# STMKernel144.net
KiCad netlist of a schematic drawn in Altium Designer
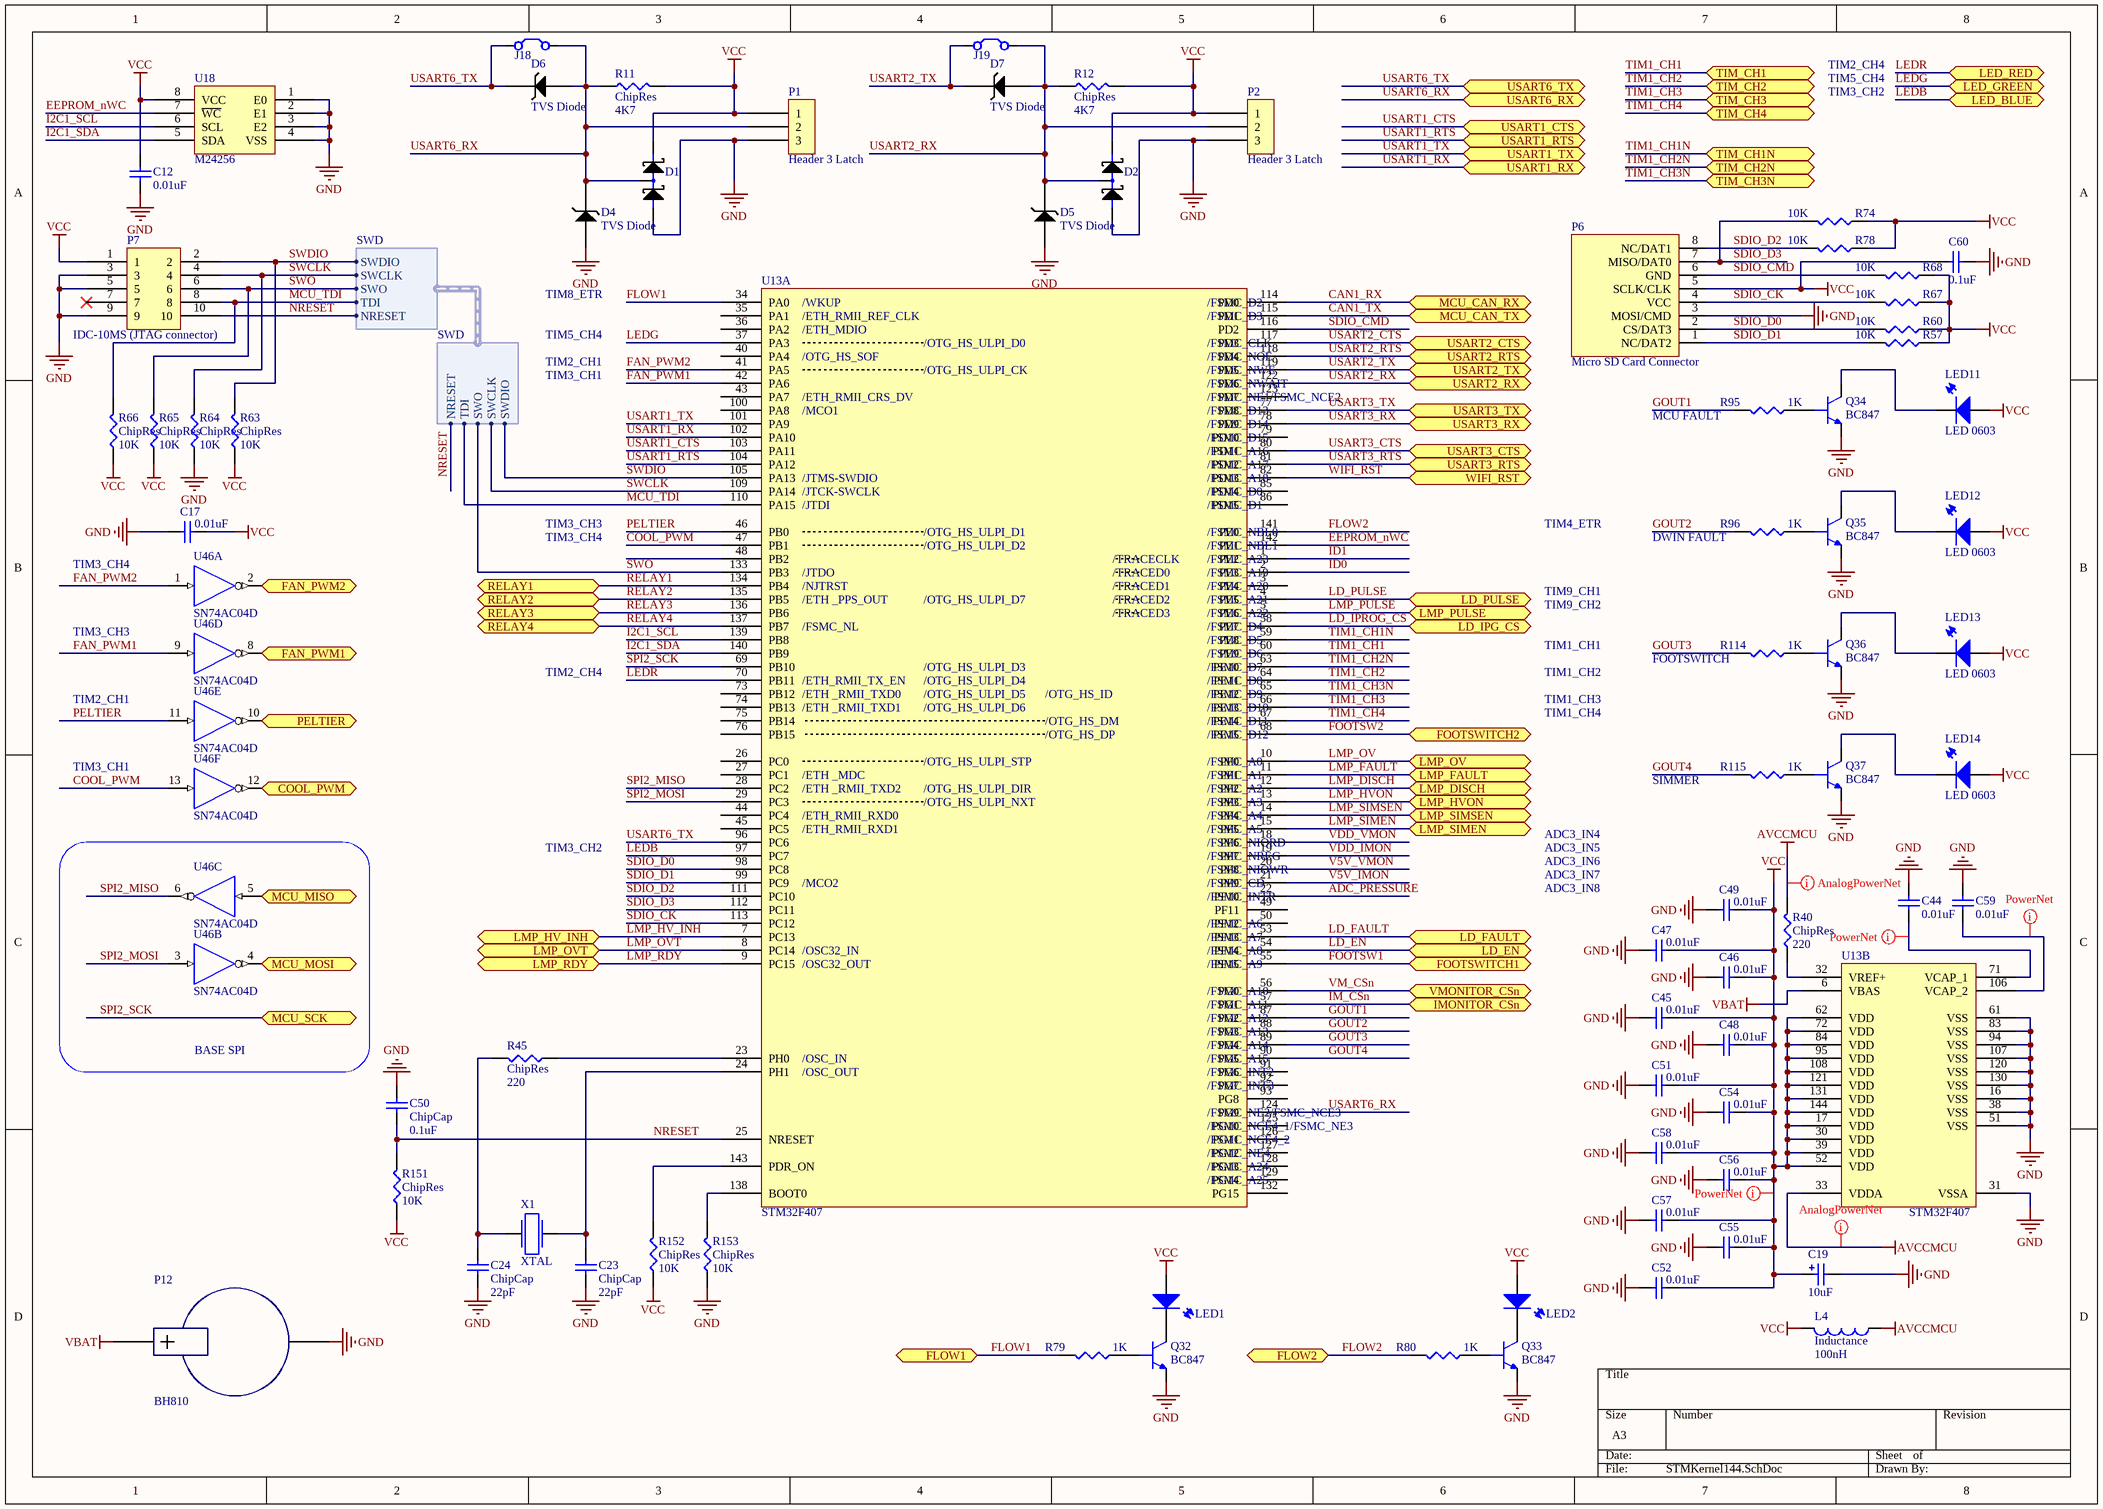
[diagram p0: STMKernel144.SchDoc]

(export (version "E")
  (design (tool "Eeschema 10.0.6"))
  (components
    (comp (ref "C12")
      (value "0.01uF")
      (footprint "CAP0805")
      (description "Capacitor")
      (fields (field (name "Comment") "ChipCap") (field (name "PUBLISHER") "Altium Limited"))
      (libsource (lib "Common Devices") (part "ChipCap"))
    )
    (comp (ref "C17")
      (value "0.01uF")
      (footprint "CAP0805")
      (description "Capacitor")
      (fields (field (name "Comment") "ChipCap") (field (name "PUBLISHER") "Altium Limited"))
      (libsource (lib "Common Devices") (part "ChipCap"))
    )
    (comp (ref "C19")
      (value "10uF")
      (footprint "CAPC7343")
      (description "Polarized Capacitor (Radial)")
      (fields (field (name "Comment") "Cap Pol SMD"))
      (libsource (lib "Common Devices") (part "Cap Pol Chip"))
    )
    (comp (ref "C23")
      (value "ChipCap")
      (footprint "CAP0805")
      (description "Capacitor")
      (fields (field (name "ALTIUM_VALUE") "22pF") (field (name "PUBLISHER") "Altium Limited"))
      (libsource (lib "Common Devices") (part "ChipCap"))
    )
    (comp (ref "C24")
      (value "ChipCap")
      (footprint "CAP0805")
      (description "Capacitor")
      (fields (field (name "ALTIUM_VALUE") "22pF") (field (name "PUBLISHER") "Altium Limited"))
      (libsource (lib "Common Devices") (part "ChipCap"))
    )
    (comp (ref "C44")
      (value "0.01uF")
      (footprint "CAP0805")
      (description "Capacitor")
      (fields (field (name "Comment") "ChipCap") (field (name "PUBLISHER") "Altium Limited"))
      (libsource (lib "Common Devices") (part "ChipCap"))
    )
    (comp (ref "C45")
      (value "0.01uF")
      (footprint "CAP0805")
      (description "Capacitor")
      (fields (field (name "Comment") "ChipCap") (field (name "PUBLISHER") "Altium Limited"))
      (libsource (lib "Common Devices") (part "ChipCap"))
    )
    (comp (ref "C46")
      (value "0.01uF")
      (footprint "CAP0805")
      (description "Capacitor")
      (fields (field (name "Comment") "ChipCap") (field (name "PUBLISHER") "Altium Limited"))
      (libsource (lib "Common Devices") (part "ChipCap"))
    )
    (comp (ref "C47")
      (value "0.01uF")
      (footprint "CAP0805")
      (description "Capacitor")
      (fields (field (name "Comment") "ChipCap") (field (name "PUBLISHER") "Altium Limited"))
      (libsource (lib "Common Devices") (part "ChipCap"))
    )
    (comp (ref "C48")
      (value "0.01uF")
      (footprint "CAP0805")
      (description "Capacitor")
      (fields (field (name "Comment") "ChipCap") (field (name "PUBLISHER") "Altium Limited"))
      (libsource (lib "Common Devices") (part "ChipCap"))
    )
    (comp (ref "C49")
      (value "0.01uF")
      (footprint "CAP0805")
      (description "Capacitor")
      (fields (field (name "Comment") "ChipCap") (field (name "PUBLISHER") "Altium Limited"))
      (libsource (lib "Common Devices") (part "ChipCap"))
    )
    (comp (ref "C50")
      (value "ChipCap")
      (footprint "CAP0805")
      (description "Capacitor")
      (fields (field (name "ALTIUM_VALUE") "0.1uF") (field (name "PUBLISHER") "Altium Limited"))
      (libsource (lib "Common Devices") (part "ChipCap"))
    )
    (comp (ref "C51")
      (value "0.01uF")
      (footprint "CAP0805")
      (description "Capacitor")
      (fields (field (name "Comment") "ChipCap") (field (name "PUBLISHER") "Altium Limited"))
      (libsource (lib "Common Devices") (part "ChipCap"))
    )
    (comp (ref "C52")
      (value "0.01uF")
      (footprint "CAP0805")
      (description "Capacitor")
      (fields (field (name "Comment") "ChipCap") (field (name "PUBLISHER") "Altium Limited"))
      (libsource (lib "Common Devices") (part "ChipCap"))
    )
    (comp (ref "C54")
      (value "0.01uF")
      (footprint "CAP0805")
      (description "Capacitor")
      (fields (field (name "Comment") "ChipCap") (field (name "PUBLISHER") "Altium Limited"))
      (libsource (lib "Common Devices") (part "ChipCap"))
    )
    (comp (ref "C55")
      (value "0.01uF")
      (footprint "CAP0805")
      (description "Capacitor")
      (fields (field (name "Comment") "ChipCap") (field (name "PUBLISHER") "Altium Limited"))
      (libsource (lib "Common Devices") (part "ChipCap"))
    )
    (comp (ref "C56")
      (value "0.01uF")
      (footprint "CAP0805")
      (description "Capacitor")
      (fields (field (name "Comment") "ChipCap") (field (name "PUBLISHER") "Altium Limited"))
      (libsource (lib "Common Devices") (part "ChipCap"))
    )
    (comp (ref "C57")
      (value "0.01uF")
      (footprint "CAP0805")
      (description "Capacitor")
      (fields (field (name "Comment") "ChipCap") (field (name "PUBLISHER") "Altium Limited"))
      (libsource (lib "Common Devices") (part "ChipCap"))
    )
    (comp (ref "C58")
      (value "0.01uF")
      (footprint "CAP0805")
      (description "Capacitor")
      (fields (field (name "Comment") "ChipCap") (field (name "PUBLISHER") "Altium Limited"))
      (libsource (lib "Common Devices") (part "ChipCap"))
    )
    (comp (ref "C59")
      (value "0.01uF")
      (footprint "CAP0805")
      (description "Capacitor")
      (fields (field (name "Comment") "ChipCap") (field (name "PUBLISHER") "Altium Limited"))
      (libsource (lib "Common Devices") (part "ChipCap"))
    )
    (comp (ref "C60")
      (value "0.1uF")
      (footprint "CAP0805")
      (description "Capacitor")
      (fields (field (name "Comment") "ChipCap") (field (name "PUBLISHER") "Altium Limited"))
      (libsource (lib "Common Devices") (part "ChipCap"))
    )
    (comp (ref "D1")
      (value "Diode Schottky")
      (footprint "SOT23")
      (description "2-Diode Schottky")
      (libsource (lib "Protection") (part "Schottky Diode"))
    )
    (comp (ref "D2")
      (value "Diode Schottky")
      (footprint "SOT23")
      (description "2-Diode Schottky")
      (libsource (lib "Protection") (part "Schottky Diode"))
    )
    (comp (ref "D4")
      (value "TVS Diode")
      (footprint "DO-214AS")
      (libsource (lib "Protection") (part "TVS Diode SMA"))
    )
    (comp (ref "D5")
      (value "TVS Diode")
      (footprint "DO-214AS")
      (libsource (lib "Protection") (part "TVS Diode SMA"))
    )
    (comp (ref "D6")
      (value "TVS Diode")
      (footprint "DO-214AS")
      (libsource (lib "Protection") (part "TVS Diode SMA"))
    )
    (comp (ref "D7")
      (value "TVS Diode")
      (footprint "DO-214AS")
      (libsource (lib "Protection") (part "TVS Diode SMA"))
    )
    (comp (ref "J18") (value "Jumper") (footprint "J0805") (libsource (lib "Common Devices") (part "Jumper")))
    (comp (ref "J19") (value "Jumper") (footprint "J0805") (libsource (lib "Common Devices") (part "Jumper")))
    (comp (ref "L4")
      (value "Inductance")
      (footprint "CM45")
      (fields (field (name "ALTIUM_VALUE") "100nH"))
      (libsource (lib "Common Devices") (part "ChipInductance"))
    )
    (comp (ref "LED1") (value "LED 0603") (footprint "LED 0603") (libsource (lib "LEDs") (part "LED0603")))
    (comp (ref "LED2") (value "LED 0603") (footprint "LED 0603") (libsource (lib "LEDs") (part "LED0603")))
    (comp (ref "LED11") (value "LED 0603") (footprint "PLCC-2") (libsource (lib "LEDs") (part "LED0603")))
    (comp (ref "LED12") (value "LED 0603") (footprint "PLCC-2") (libsource (lib "LEDs") (part "LED0603")))
    (comp (ref "LED13") (value "LED 0603") (footprint "PLCC-2") (libsource (lib "LEDs") (part "LED0603")))
    (comp (ref "LED14") (value "LED 0603") (footprint "PLCC-2") (libsource (lib "LEDs") (part "LED0603")))
    (comp (ref "P1")
      (value "Header 3 Latch")
      (footprint "Header 3 latch")
      (description "Header 3 with latch")
      (libsource (lib "IndustrialConnectors") (part "Header 3 latch"))
    )
    (comp (ref "P2")
      (value "Header 3 Latch")
      (footprint "Header 3 latch")
      (description "Header 3 with latch")
      (libsource (lib "IndustrialConnectors") (part "Header 3 latch"))
    )
    (comp (ref "P6")
      (value "Micro SD Card Connector")
      (footprint "WR-CRD SD Micro")
      (libsource (lib "Connectors") (part "MicroSDHeader8"))
    )
    (comp (ref "P7")
      (value "IDC-10MS (JTAG connector)")
      (footprint "IDC-10MS(MR)")
      (libsource (lib "Connectors") (part "IDC-10MS (JTAG connector)"))
    )
    (comp (ref "P12") (value "BH810") (footprint "BH810") (libsource (lib "BatteryHolder") (part "BH810")))
    (comp (ref "Q32")
      (value "BC847")
      (footprint "SOT23")
      (description "NPN transistor")
      (libsource (lib "BJT") (part "BC847"))
    )
    (comp (ref "Q33")
      (value "BC847")
      (footprint "SOT23")
      (description "NPN transistor")
      (libsource (lib "BJT") (part "BC847"))
    )
    (comp (ref "Q34")
      (value "BC847")
      (footprint "SOT23")
      (description "NPN transistor")
      (libsource (lib "BJT") (part "BC847"))
    )
    (comp (ref "Q35")
      (value "BC847")
      (footprint "SOT23")
      (description "NPN transistor")
      (libsource (lib "BJT") (part "BC847"))
    )
    (comp (ref "Q36")
      (value "BC847")
      (footprint "SOT23")
      (description "NPN transistor")
      (libsource (lib "BJT") (part "BC847"))
    )
    (comp (ref "Q37")
      (value "BC847")
      (footprint "SOT23")
      (description "NPN transistor")
      (libsource (lib "BJT") (part "BC847"))
    )
    (comp (ref "R11")
      (value "ChipRes")
      (footprint "RES0805")
      (description "Chip resistor")
      (fields (field (name "ALTIUM_VALUE") "4K7"))
      (libsource (lib "Common Devices") (part "ChipRes"))
    )
    (comp (ref "R12")
      (value "ChipRes")
      (footprint "RES0805")
      (description "Chip resistor")
      (fields (field (name "ALTIUM_VALUE") "4K7"))
      (libsource (lib "Common Devices") (part "ChipRes"))
    )
    (comp (ref "R40")
      (value "ChipRes")
      (footprint "RES0805")
      (description "Chip resistor")
      (fields (field (name "ALTIUM_VALUE") "220"))
      (libsource (lib "Common Devices") (part "ChipRes"))
    )
    (comp (ref "R45")
      (value "ChipRes")
      (footprint "RES0805")
      (description "Chip resistor")
      (fields (field (name "ALTIUM_VALUE") "220"))
      (libsource (lib "Common Devices") (part "ChipRes"))
    )
    (comp (ref "R57")
      (value "10K")
      (footprint "RES0805")
      (description "Chip resistor")
      (fields (field (name "Comment") "ChipRes"))
      (libsource (lib "Common Devices") (part "ChipRes"))
    )
    (comp (ref "R60")
      (value "10K")
      (footprint "RES0805")
      (description "Chip resistor")
      (fields (field (name "Comment") "ChipRes"))
      (libsource (lib "Common Devices") (part "ChipRes"))
    )
    (comp (ref "R63")
      (value "ChipRes")
      (footprint "RES0805")
      (description "Chip resistor")
      (fields (field (name "ALTIUM_VALUE") "10K"))
      (libsource (lib "Common Devices") (part "ChipRes"))
    )
    (comp (ref "R64")
      (value "ChipRes")
      (footprint "RES0805")
      (description "Chip resistor")
      (fields (field (name "ALTIUM_VALUE") "10K"))
      (libsource (lib "Common Devices") (part "ChipRes"))
    )
    (comp (ref "R65")
      (value "ChipRes")
      (footprint "RES0805")
      (description "Chip resistor")
      (fields (field (name "ALTIUM_VALUE") "10K"))
      (libsource (lib "Common Devices") (part "ChipRes"))
    )
    (comp (ref "R66")
      (value "ChipRes")
      (footprint "RES0805")
      (description "Chip resistor")
      (fields (field (name "ALTIUM_VALUE") "10K"))
      (libsource (lib "Common Devices") (part "ChipRes"))
    )
    (comp (ref "R67")
      (value "10K")
      (footprint "RES0805")
      (description "Chip resistor")
      (fields (field (name "Comment") "ChipRes"))
      (libsource (lib "Common Devices") (part "ChipRes"))
    )
    (comp (ref "R68")
      (value "10K")
      (footprint "RES0805")
      (description "Chip resistor")
      (fields (field (name "Comment") "ChipRes"))
      (libsource (lib "Common Devices") (part "ChipRes"))
    )
    (comp (ref "R74")
      (value "10K")
      (footprint "RES0805")
      (description "Chip resistor")
      (fields (field (name "Comment") "ChipRes"))
      (libsource (lib "Common Devices") (part "ChipRes"))
    )
    (comp (ref "R78")
      (value "10K")
      (footprint "RES0805")
      (description "Chip resistor")
      (fields (field (name "Comment") "ChipRes"))
      (libsource (lib "Common Devices") (part "ChipRes"))
    )
    (comp (ref "R79")
      (value "1K")
      (footprint "RES0805")
      (description "Chip resistor")
      (fields (field (name "Comment") "ChipRes"))
      (libsource (lib "Common Devices") (part "ChipRes"))
    )
    (comp (ref "R80")
      (value "1K")
      (footprint "RES0805")
      (description "Chip resistor")
      (fields (field (name "Comment") "ChipRes"))
      (libsource (lib "Common Devices") (part "ChipRes"))
    )
    (comp (ref "R95")
      (value "1K")
      (footprint "RES0805")
      (description "Chip resistor")
      (fields (field (name "Comment") "ChipRes"))
      (libsource (lib "Common Devices") (part "ChipRes"))
    )
    (comp (ref "R96")
      (value "1K")
      (footprint "RES0805")
      (description "Chip resistor")
      (fields (field (name "Comment") "ChipRes"))
      (libsource (lib "Common Devices") (part "ChipRes"))
    )
    (comp (ref "R114")
      (value "1K")
      (footprint "RES0805")
      (description "Chip resistor")
      (fields (field (name "Comment") "ChipRes"))
      (libsource (lib "Common Devices") (part "ChipRes"))
    )
    (comp (ref "R115")
      (value "1K")
      (footprint "RES0805")
      (description "Chip resistor")
      (fields (field (name "Comment") "ChipRes"))
      (libsource (lib "Common Devices") (part "ChipRes"))
    )
    (comp (ref "R151")
      (value "ChipRes")
      (footprint "RES0805")
      (description "Chip resistor")
      (fields (field (name "ALTIUM_VALUE") "10K"))
      (libsource (lib "Common Devices") (part "ChipRes"))
    )
    (comp (ref "R152")
      (value "ChipRes")
      (footprint "RES0805")
      (description "Chip resistor")
      (fields (field (name "ALTIUM_VALUE") "10K"))
      (libsource (lib "Common Devices") (part "ChipRes"))
    )
    (comp (ref "R153")
      (value "ChipRes")
      (footprint "RES0805")
      (description "Chip resistor")
      (fields (field (name "ALTIUM_VALUE") "10K"))
      (libsource (lib "Common Devices") (part "ChipRes"))
    )
    (comp (ref "U13")
      (value "STM32F407")
      (footprint "LQFP144")
      (description "ST Microcontroller ARM 32-bit Cortex M4")
      (libsource (lib "ST ARM32") (part "STM32F407ZGT6"))
    )
    (comp (ref "U18")
      (value "M24256")
      (footprint "SOIC8")
      (description "256 Kbit I2C EEPROM")
      (libsource (lib "ST EEPROM") (part "M24256"))
    )
    (comp (ref "U46")
      (value "SN74AC04D")
      (footprint "D014_N")
      (description "Hex Inverter")
      (fields (field (name "PUBLISHER") "Altium Limited"))
      (libsource (lib "TI Logic Gate 1") (part "SN74AC04D"))
    )
    (comp (ref "X1")
      (value "XTAL")
      (footprint "BCY-W2/E4.7")
      (description "Quartz crystall oscillator")
      (libsource (lib "Common Devices") (part "Crystall oscillator"))
    )
  )
  (nets
    (net (code "2") (name "/ADC_PRESSURE") (class "Default")
      (node (ref "U13") (pin "22") (pinfunction "PF10_22") (pintype "passive"))
    )
    (net (code "3") (name "/CAN1_RX") (class "Default")
      (node (ref "U13") (pin "114") (pinfunction "PD0_114") (pintype "passive"))
    )
    (net (code "4") (name "/CAN1_TX") (class "Default")
      (node (ref "U13") (pin "115") (pinfunction "PD1_115") (pintype "passive"))
    )
    (net (code "5") (name "/COOL_PWM") (class "Default")
      (node (ref "U13") (pin "47") (pinfunction "PB1_47") (pintype "passive"))
      (node (ref "U46") (pin "13") (pinfunction "A_13") (pintype "input"))
    )
    (net (code "6") (name "/EEPROM_nWC") (class "Default")
      (node (ref "U13") (pin "142") (pinfunction "PE1_142") (pintype "passive"))
      (node (ref "U18") (pin "7") (pinfunction "~{WC}_7") (pintype "passive"))
    )
    (net (code "7") (name "/FAN_PWM1") (class "Default")
      (node (ref "U13") (pin "42") (pinfunction "PA6_42") (pintype "passive"))
      (node (ref "U46") (pin "9") (pinfunction "A_9") (pintype "input"))
    )
    (net (code "8") (name "/FAN_PWM2") (class "Default")
      (node (ref "U13") (pin "41") (pinfunction "PA5_41") (pintype "passive"))
      (node (ref "U46") (pin "1") (pinfunction "A_1") (pintype "input"))
    )
    (net (code "9") (name "/FLOW1") (class "Default")
      (node (ref "R79") (pin "1") (pintype "passive"))
      (node (ref "U13") (pin "34") (pinfunction "PA0_34") (pintype "passive"))
    )
    (net (code "10") (name "/FLOW2") (class "Default")
      (node (ref "R80") (pin "1") (pintype "passive"))
      (node (ref "U13") (pin "141") (pinfunction "PE0_141") (pintype "passive"))
    )
    (net (code "11") (name "/FOOTSW1") (class "Default")
      (node (ref "U13") (pin "55") (pinfunction "PF15_55") (pintype "passive"))
    )
    (net (code "12") (name "/FOOTSW2") (class "Default")
      (node (ref "U13") (pin "68") (pinfunction "PE15_68") (pintype "passive"))
    )
    (net (code "13") (name "/GOUT1") (class "Default")
      (node (ref "R95") (pin "1") (pintype "passive"))
      (node (ref "U13") (pin "87") (pinfunction "PG2_87") (pintype "passive"))
    )
    (net (code "14") (name "/GOUT2") (class "Default")
      (node (ref "R96") (pin "1") (pintype "passive"))
      (node (ref "U13") (pin "88") (pinfunction "PG3_88") (pintype "passive"))
    )
    (net (code "15") (name "/GOUT3") (class "Default")
      (node (ref "R114") (pin "1") (pintype "passive"))
      (node (ref "U13") (pin "89") (pinfunction "PG4_89") (pintype "passive"))
    )
    (net (code "16") (name "/GOUT4") (class "Default")
      (node (ref "R115") (pin "1") (pintype "passive"))
      (node (ref "U13") (pin "90") (pinfunction "PG5_90") (pintype "passive"))
    )
    (net (code "17") (name "/I2C1_SCL") (class "Default")
      (node (ref "U13") (pin "139") (pinfunction "PB8_139") (pintype "passive"))
      (node (ref "U18") (pin "6") (pinfunction "SCL_6") (pintype "passive"))
    )
    (net (code "18") (name "/I2C1_SDA") (class "Default")
      (node (ref "U13") (pin "140") (pinfunction "PB9_140") (pintype "passive"))
      (node (ref "U18") (pin "5") (pinfunction "SDA_5") (pintype "passive"))
    )
    (net (code "19") (name "/ID0") (class "Default")
      (node (ref "U13") (pin "2") (pinfunction "PE3_2") (pintype "passive"))
    )
    (net (code "20") (name "/ID1") (class "Default")
      (node (ref "U13") (pin "1") (pinfunction "PE2_1") (pintype "passive"))
    )
    (net (code "21") (name "/IM_CSn") (class "Default")
      (node (ref "U13") (pin "57") (pinfunction "PG1_57") (pintype "passive"))
    )
    (net (code "22") (name "/LD_EN") (class "Default")
      (node (ref "U13") (pin "54") (pinfunction "PF14_54") (pintype "passive"))
    )
    (net (code "23") (name "/LD_FAULT") (class "Default")
      (node (ref "U13") (pin "53") (pinfunction "PF13_53") (pintype "passive"))
    )
    (net (code "24") (name "/LD_IPROG_CS") (class "Default")
      (node (ref "U13") (pin "58") (pinfunction "PE7_58") (pintype "passive"))
    )
    (net (code "25") (name "/LD_PULSE") (class "Default")
      (node (ref "U13") (pin "4") (pinfunction "PE5_4") (pintype "passive"))
    )
    (net (code "26") (name "/LEDB") (class "Default")
      (node (ref "U13") (pin "97") (pinfunction "PC7_97") (pintype "passive"))
    )
    (net (code "27") (name "/LEDG") (class "Default")
      (node (ref "U13") (pin "37") (pinfunction "PA3_37") (pintype "passive"))
    )
    (net (code "28") (name "/LEDR") (class "Default")
      (node (ref "U13") (pin "70") (pinfunction "PB11_70") (pintype "passive"))
    )
    (net (code "29") (name "/LMP_DISCH") (class "Default")
      (node (ref "U13") (pin "12") (pinfunction "PF2_12") (pintype "passive"))
    )
    (net (code "30") (name "/LMP_FAULT") (class "Default")
      (node (ref "U13") (pin "11") (pinfunction "PF1_11") (pintype "passive"))
    )
    (net (code "31") (name "/LMP_HVON") (class "Default")
      (node (ref "U13") (pin "13") (pinfunction "PF3_13") (pintype "passive"))
    )
    (net (code "32") (name "/LMP_HV_INH") (class "Default")
      (node (ref "U13") (pin "7") (pinfunction "PC13_7") (pintype "passive"))
    )
    (net (code "33") (name "/LMP_OV") (class "Default")
      (node (ref "U13") (pin "10") (pinfunction "PF0_10") (pintype "passive"))
    )
    (net (code "34") (name "/LMP_OVT") (class "Default")
      (node (ref "U13") (pin "8") (pinfunction "PC14_8") (pintype "passive"))
    )
    (net (code "35") (name "/LMP_PULSE") (class "Default")
      (node (ref "U13") (pin "5") (pinfunction "PE6_5") (pintype "passive"))
    )
    (net (code "36") (name "/LMP_RDY") (class "Default")
      (node (ref "U13") (pin "9") (pinfunction "PC15_9") (pintype "passive"))
    )
    (net (code "37") (name "/LMP_SIMEN") (class "Default")
      (node (ref "U13") (pin "15") (pinfunction "PF5_15") (pintype "passive"))
    )
    (net (code "38") (name "/LMP_SIMSEN") (class "Default")
      (node (ref "U13") (pin "14") (pinfunction "PF4_14") (pintype "passive"))
    )
    (net (code "39") (name "/MCU_MISO") (class "Default")
      (node (ref "U46") (pin "5") (pinfunction "A_5") (pintype "input"))
    )
    (net (code "40") (name "/MCU_MOSI") (class "Default")
      (node (ref "U46") (pin "4") (pinfunction "Y_4") (pintype "output"))
    )
    (net (code "41") (name "/MCU_TDI") (class "Default")
      (node (ref "P7") (pin "8") (pinfunction "8_8") (pintype "passive"))
      (node (ref "R66") (pin "2") (pintype "passive"))
      (node (ref "U13") (pin "110") (pinfunction "PA15_110") (pintype "passive"))
    )
    (net (code "42") (name "/NRESET") (class "Default")
      (node (ref "C50") (pin "1") (pinfunction "1_1") (pintype "passive"))
      (node (ref "P7") (pin "10") (pinfunction "10_10") (pintype "passive"))
      (node (ref "R151") (pin "2") (pintype "passive"))
      (node (ref "U13") (pin "25") (pinfunction "NRESET_25") (pintype "passive"))
    )
    (net (code "43") (name "/PELTIER") (class "Default")
      (node (ref "U13") (pin "46") (pinfunction "PB0_46") (pintype "passive"))
      (node (ref "U46") (pin "11") (pinfunction "A_11") (pintype "input"))
    )
    (net (code "44") (name "/RELAY1") (class "Default")
      (node (ref "U13") (pin "134") (pinfunction "PB4_134") (pintype "passive"))
    )
    (net (code "45") (name "/RELAY2") (class "Default")
      (node (ref "U13") (pin "135") (pinfunction "PB5_135") (pintype "passive"))
    )
    (net (code "46") (name "/RELAY3") (class "Default")
      (node (ref "U13") (pin "136") (pinfunction "PB6_136") (pintype "passive"))
    )
    (net (code "47") (name "/RELAY4") (class "Default")
      (node (ref "U13") (pin "137") (pinfunction "PB7_137") (pintype "passive"))
    )
    (net (code "48") (name "/SDIO_CK") (class "Default")
      (node (ref "P6") (pin "4") (pinfunction "VCC_4") (pintype "passive"))
      (node (ref "R67") (pin "1") (pintype "passive"))
      (node (ref "U13") (pin "113") (pinfunction "PC12_113") (pintype "passive"))
    )
    (net (code "49") (name "/SDIO_CMD") (class "Default")
      (node (ref "P6") (pin "6") (pinfunction "GND_6") (pintype "passive"))
      (node (ref "R68") (pin "1") (pintype "passive"))
      (node (ref "U13") (pin "116") (pinfunction "PD2_116") (pintype "passive"))
    )
    (net (code "50") (name "/SDIO_D0") (class "Default")
      (node (ref "P6") (pin "2") (pinfunction "CS/DAT3_2") (pintype "passive"))
      (node (ref "R60") (pin "1") (pintype "passive"))
      (node (ref "U13") (pin "98") (pinfunction "PC8_98") (pintype "passive"))
    )
    (net (code "51") (name "/SDIO_D1") (class "Default")
      (node (ref "P6") (pin "1") (pinfunction "NC/DAT2_1") (pintype "passive"))
      (node (ref "R57") (pin "1") (pintype "passive"))
      (node (ref "U13") (pin "99") (pinfunction "PC9_99") (pintype "passive"))
    )
    (net (code "52") (name "/SDIO_D2") (class "Default")
      (node (ref "P6") (pin "8") (pinfunction "NC/DAT1_8") (pintype "passive"))
      (node (ref "R78") (pin "1") (pintype "passive"))
      (node (ref "U13") (pin "111") (pinfunction "PC10_111") (pintype "passive"))
    )
    (net (code "53") (name "/SDIO_D3") (class "Default")
      (node (ref "P6") (pin "7") (pinfunction "MISO/DAT0_7") (pintype "passive"))
      (node (ref "R74") (pin "1") (pintype "passive"))
      (node (ref "U13") (pin "112") (pinfunction "PC11_112") (pintype "passive"))
    )
    (net (code "54") (name "/SPI2_MISO") (class "Default")
      (node (ref "U13") (pin "28") (pinfunction "PC2_28") (pintype "passive"))
      (node (ref "U46") (pin "6") (pinfunction "Y_6") (pintype "output"))
    )
    (net (code "55") (name "/SPI2_MOSI") (class "Default")
      (node (ref "U13") (pin "29") (pinfunction "PC3_29") (pintype "passive"))
      (node (ref "U46") (pin "3") (pinfunction "A_3") (pintype "input"))
    )
    (net (code "56") (name "/SPI2_SCK") (class "Default")
      (node (ref "U13") (pin "69") (pinfunction "PB10_69") (pintype "passive"))
    )
    (net (code "57") (name "/SWCLK") (class "Default")
      (node (ref "P7") (pin "4") (pinfunction "4_4") (pintype "passive"))
      (node (ref "R64") (pin "2") (pintype "passive"))
      (node (ref "U13") (pin "109") (pinfunction "PA14_109") (pintype "passive"))
    )
    (net (code "58") (name "/SWDIO") (class "Default")
      (node (ref "P7") (pin "2") (pinfunction "2_2") (pintype "passive"))
      (node (ref "R63") (pin "2") (pintype "passive"))
      (node (ref "U13") (pin "105") (pinfunction "PA13_105") (pintype "passive"))
    )
    (net (code "59") (name "/SWO") (class "Default")
      (node (ref "P7") (pin "6") (pinfunction "6_6") (pintype "passive"))
      (node (ref "R65") (pin "2") (pintype "passive"))
      (node (ref "U13") (pin "133") (pinfunction "PB3_133") (pintype "passive"))
    )
    (net (code "60") (name "/TIM1_CH1") (class "Default")
      (node (ref "U13") (pin "60") (pinfunction "PE9_60") (pintype "passive"))
    )
    (net (code "61") (name "/TIM1_CH1N") (class "Default")
      (node (ref "U13") (pin "59") (pinfunction "PE8_59") (pintype "passive"))
    )
    (net (code "62") (name "/TIM1_CH2") (class "Default")
      (node (ref "U13") (pin "64") (pinfunction "PE11_64") (pintype "passive"))
    )
    (net (code "63") (name "/TIM1_CH2N") (class "Default")
      (node (ref "U13") (pin "63") (pinfunction "PE10_63") (pintype "passive"))
    )
    (net (code "64") (name "/TIM1_CH3") (class "Default")
      (node (ref "U13") (pin "66") (pinfunction "PE13_66") (pintype "passive"))
    )
    (net (code "65") (name "/TIM1_CH3N") (class "Default")
      (node (ref "U13") (pin "65") (pinfunction "PE12_65") (pintype "passive"))
    )
    (net (code "66") (name "/TIM1_CH4") (class "Default")
      (node (ref "U13") (pin "67") (pinfunction "PE14_67") (pintype "passive"))
    )
    (net (code "67") (name "/USART1_CTS") (class "Default")
      (node (ref "U13") (pin "103") (pinfunction "PA11_103") (pintype "passive"))
    )
    (net (code "68") (name "/USART1_RTS") (class "Default")
      (node (ref "U13") (pin "104") (pinfunction "PA12_104") (pintype "passive"))
    )
    (net (code "69") (name "/USART1_RX") (class "Default")
      (node (ref "U13") (pin "102") (pinfunction "PA10_102") (pintype "passive"))
    )
    (net (code "70") (name "/USART1_TX") (class "Default")
      (node (ref "U13") (pin "101") (pinfunction "PA9_101") (pintype "passive"))
    )
    (net (code "71") (name "/USART2_CTS") (class "Default")
      (node (ref "U13") (pin "117") (pinfunction "PD3_117") (pintype "passive"))
    )
    (net (code "72") (name "/USART2_RTS") (class "Default")
      (node (ref "U13") (pin "118") (pinfunction "PD4_118") (pintype "passive"))
    )
    (net (code "73") (name "/USART2_RX") (class "Default")
      (node (ref "D2") (pin "3") (pinfunction "3_3") (pintype "passive"))
      (node (ref "D5") (pin "1") (pinfunction "1_1") (pintype "passive"))
      (node (ref "D7") (pin "2") (pinfunction "2_2") (pintype "passive"))
      (node (ref "J19") (pin "1") (pinfunction "1_1") (pintype "passive"))
      (node (ref "P2") (pin "2") (pinfunction "2_2") (pintype "passive"))
      (node (ref "R12") (pin "1") (pintype "passive"))
      (node (ref "U13") (pin "122") (pinfunction "PD6_122") (pintype "passive"))
    )
    (net (code "74") (name "/USART2_TX") (class "Default")
      (node (ref "D7") (pin "1") (pinfunction "1_1") (pintype "passive"))
      (node (ref "J19") (pin "0") (pinfunction "0_0") (pintype "passive"))
      (node (ref "U13") (pin "119") (pinfunction "PD5_119") (pintype "passive"))
    )
    (net (code "75") (name "/USART3_CTS") (class "Default")
      (node (ref "U13") (pin "80") (pinfunction "PD11_80") (pintype "passive"))
    )
    (net (code "76") (name "/USART3_RTS") (class "Default")
      (node (ref "U13") (pin "81") (pinfunction "PD12_81") (pintype "passive"))
    )
    (net (code "77") (name "/USART3_RX") (class "Default")
      (node (ref "U13") (pin "78") (pinfunction "PD9_78") (pintype "passive"))
    )
    (net (code "78") (name "/USART3_TX") (class "Default")
      (node (ref "U13") (pin "77") (pinfunction "PD8_77") (pintype "passive"))
    )
    (net (code "79") (name "/USART6_RX") (class "Default")
      (node (ref "D1") (pin "3") (pinfunction "3_3") (pintype "passive"))
      (node (ref "D4") (pin "1") (pinfunction "1_1") (pintype "passive"))
      (node (ref "D6") (pin "2") (pinfunction "2_2") (pintype "passive"))
      (node (ref "J18") (pin "1") (pinfunction "1_1") (pintype "passive"))
      (node (ref "P1") (pin "2") (pinfunction "2_2") (pintype "passive"))
      (node (ref "R11") (pin "1") (pintype "passive"))
      (node (ref "U13") (pin "124") (pinfunction "PG9_124") (pintype "passive"))
    )
    (net (code "80") (name "/USART6_TX") (class "Default")
      (node (ref "D6") (pin "1") (pinfunction "1_1") (pintype "passive"))
      (node (ref "J18") (pin "0") (pinfunction "0_0") (pintype "passive"))
      (node (ref "U13") (pin "96") (pinfunction "PC6_96") (pintype "passive"))
    )
    (net (code "81") (name "/V5V_IMON") (class "Default")
      (node (ref "U13") (pin "21") (pinfunction "PF9_21") (pintype "passive"))
    )
    (net (code "82") (name "/V5V_VMON") (class "Default")
      (node (ref "U13") (pin "20") (pinfunction "PF8_20") (pintype "passive"))
    )
    (net (code "83") (name "/VDD_IMON") (class "Default")
      (node (ref "U13") (pin "19") (pinfunction "PF7_19") (pintype "passive"))
    )
    (net (code "84") (name "/VDD_VMON") (class "Default")
      (node (ref "U13") (pin "18") (pinfunction "PF6_18") (pintype "passive"))
    )
    (net (code "85") (name "/VM_CSn") (class "Default")
      (node (ref "U13") (pin "56") (pinfunction "PG0_56") (pintype "passive"))
    )
    (net (code "86") (name "/WIFI_RST") (class "Default")
      (node (ref "U13") (pin "82") (pinfunction "PD13_82") (pintype "passive"))
    )
    (net (code "88") (name "AVCCMCU") (class "Default")
      (node (ref "L4") (pin "2") (pintype "passive"))
      (node (ref "R40") (pin "2") (pintype "passive"))
      (node (ref "U13") (pin "33") (pinfunction "VDDA_33") (pintype "passive"))
    )
    (net (code "89") (name "GND") (class "Default")
      (node (ref "C12") (pin "1") (pinfunction "1_1") (pintype "passive"))
      (node (ref "C17") (pin "1") (pinfunction "1_1") (pintype "passive"))
      (node (ref "C19") (pin "2") (pinfunction "2_2") (pintype "passive"))
      (node (ref "C23") (pin "1") (pinfunction "1_1") (pintype "passive"))
      (node (ref "C24") (pin "1") (pinfunction "1_1") (pintype "passive"))
      (node (ref "C44") (pin "1") (pinfunction "1_1") (pintype "passive"))
      (node (ref "C45") (pin "2") (pinfunction "2_2") (pintype "passive"))
      (node (ref "C46") (pin "2") (pinfunction "2_2") (pintype "passive"))
      (node (ref "C47") (pin "2") (pinfunction "2_2") (pintype "passive"))
      (node (ref "C48") (pin "2") (pinfunction "2_2") (pintype "passive"))
      (node (ref "C49") (pin "2") (pinfunction "2_2") (pintype "passive"))
      (node (ref "C50") (pin "2") (pinfunction "2_2") (pintype "passive"))
      (node (ref "C51") (pin "2") (pinfunction "2_2") (pintype "passive"))
      (node (ref "C52") (pin "1") (pinfunction "1_1") (pintype "passive"))
      (node (ref "C54") (pin "2") (pinfunction "2_2") (pintype "passive"))
      (node (ref "C55") (pin "2") (pinfunction "2_2") (pintype "passive"))
      (node (ref "C56") (pin "2") (pinfunction "2_2") (pintype "passive"))
      (node (ref "C57") (pin "2") (pinfunction "2_2") (pintype "passive"))
      (node (ref "C58") (pin "2") (pinfunction "2_2") (pintype "passive"))
      (node (ref "C59") (pin "1") (pinfunction "1_1") (pintype "passive"))
      (node (ref "C60") (pin "2") (pinfunction "2_2") (pintype "passive"))
      (node (ref "D1") (pin "1") (pinfunction "1_1") (pintype "passive"))
      (node (ref "D2") (pin "1") (pinfunction "1_1") (pintype "passive"))
      (node (ref "D4") (pin "2") (pinfunction "2_2") (pintype "passive"))
      (node (ref "D5") (pin "2") (pinfunction "2_2") (pintype "passive"))
      (node (ref "P1") (pin "3") (pinfunction "3_3") (pintype "passive"))
      (node (ref "P12") (pin "1") (pinfunction "BN_1") (pintype "passive"))
      (node (ref "P2") (pin "3") (pinfunction "3_3") (pintype "passive"))
      (node (ref "P6") (pin "3") (pinfunction "MOSI/CMD_3") (pintype "passive"))
      (node (ref "P7") (pin "3") (pinfunction "3_3") (pintype "passive"))
      (node (ref "P7") (pin "5") (pinfunction "5_5") (pintype "passive"))
      (node (ref "P7") (pin "9") (pinfunction "9_9") (pintype "passive"))
      (node (ref "Q32") (pin "2") (pinfunction "2_2") (pintype "passive"))
      (node (ref "Q33") (pin "2") (pinfunction "2_2") (pintype "passive"))
      (node (ref "Q34") (pin "2") (pinfunction "2_2") (pintype "passive"))
      (node (ref "Q35") (pin "2") (pinfunction "2_2") (pintype "passive"))
      (node (ref "Q36") (pin "2") (pinfunction "2_2") (pintype "passive"))
      (node (ref "Q37") (pin "2") (pinfunction "2_2") (pintype "passive"))
      (node (ref "R153") (pin "1") (pintype "passive"))
      (node (ref "R64") (pin "1") (pintype "passive"))
      (node (ref "U13") (pin "107") (pinfunction "VSS_107") (pintype "passive"))
      (node (ref "U13") (pin "120") (pinfunction "VSS_120") (pintype "passive"))
      (node (ref "U13") (pin "130") (pinfunction "VSS_130") (pintype "passive"))
      (node (ref "U13") (pin "16") (pinfunction "VSS_16") (pintype "passive"))
      (node (ref "U13") (pin "31") (pinfunction "VSSA_31") (pintype "passive"))
      (node (ref "U13") (pin "38") (pinfunction "VSS_38") (pintype "passive"))
      (node (ref "U13") (pin "51") (pinfunction "VSS_51") (pintype "passive"))
      (node (ref "U13") (pin "61") (pinfunction "VSS_61") (pintype "passive"))
      (node (ref "U13") (pin "83") (pinfunction "VSS_83") (pintype "passive"))
      (node (ref "U13") (pin "94") (pinfunction "VSS_94") (pintype "passive"))
      (node (ref "U18") (pin "1") (pinfunction "E0_1") (pintype "passive"))
      (node (ref "U18") (pin "2") (pinfunction "E1_2") (pintype "passive"))
      (node (ref "U18") (pin "3") (pinfunction "E2_3") (pintype "passive"))
      (node (ref "U18") (pin "4") (pinfunction "VSS_4") (pintype "passive"))
      (node (ref "U46") (pin "7") (pinfunction "GND_7") (pintype "power_in"))
    )
    (net (code "90") (name "Net-(C24-Pad2)") (class "Default")
      (node (ref "C24") (pin "2") (pinfunction "2_2") (pintype "passive"))
      (node (ref "R45") (pin "2") (pintype "passive"))
      (node (ref "X1") (pin "1") (pinfunction "1_1") (pintype "passive"))
    )
    (net (code "91") (name "Net-(LED1-Pad1)") (class "Default")
      (node (ref "LED1") (pin "1") (pinfunction "1_1") (pintype "passive"))
      (node (ref "Q32") (pin "3") (pinfunction "3_3") (pintype "passive"))
    )
    (net (code "92") (name "Net-(LED2-Pad1)") (class "Default")
      (node (ref "LED2") (pin "1") (pinfunction "1_1") (pintype "passive"))
      (node (ref "Q33") (pin "3") (pinfunction "3_3") (pintype "passive"))
    )
    (net (code "93") (name "Net-(LED11-Pad1)") (class "Default")
      (node (ref "LED11") (pin "1") (pinfunction "1_1") (pintype "passive"))
      (node (ref "Q34") (pin "3") (pinfunction "3_3") (pintype "passive"))
    )
    (net (code "94") (name "Net-(LED12-Pad1)") (class "Default")
      (node (ref "LED12") (pin "1") (pinfunction "1_1") (pintype "passive"))
      (node (ref "Q35") (pin "3") (pinfunction "3_3") (pintype "passive"))
    )
    (net (code "95") (name "Net-(LED13-Pad1)") (class "Default")
      (node (ref "LED13") (pin "1") (pinfunction "1_1") (pintype "passive"))
      (node (ref "Q36") (pin "3") (pinfunction "3_3") (pintype "passive"))
    )
    (net (code "96") (name "Net-(LED14-Pad1)") (class "Default")
      (node (ref "LED14") (pin "1") (pinfunction "1_1") (pintype "passive"))
      (node (ref "Q37") (pin "3") (pinfunction "3_3") (pintype "passive"))
    )
    (net (code "97") (name "Net-(Q32-Pad1)") (class "Default")
      (node (ref "Q32") (pin "1") (pinfunction "1_1") (pintype "passive"))
      (node (ref "R79") (pin "2") (pintype "passive"))
    )
    (net (code "98") (name "Net-(Q33-Pad1)") (class "Default")
      (node (ref "Q33") (pin "1") (pinfunction "1_1") (pintype "passive"))
      (node (ref "R80") (pin "2") (pintype "passive"))
    )
    (net (code "99") (name "Net-(Q34-Pad1)") (class "Default")
      (node (ref "Q34") (pin "1") (pinfunction "1_1") (pintype "passive"))
      (node (ref "R95") (pin "2") (pintype "passive"))
    )
    (net (code "100") (name "Net-(Q35-Pad1)") (class "Default")
      (node (ref "Q35") (pin "1") (pinfunction "1_1") (pintype "passive"))
      (node (ref "R96") (pin "2") (pintype "passive"))
    )
    (net (code "101") (name "Net-(Q36-Pad1)") (class "Default")
      (node (ref "Q36") (pin "1") (pinfunction "1_1") (pintype "passive"))
      (node (ref "R114") (pin "2") (pintype "passive"))
    )
    (net (code "102") (name "Net-(Q37-Pad1)") (class "Default")
      (node (ref "Q37") (pin "1") (pinfunction "1_1") (pintype "passive"))
      (node (ref "R115") (pin "2") (pintype "passive"))
    )
    (net (code "103") (name "Net-(U13A-BOOT0)") (class "Default")
      (node (ref "R153") (pin "2") (pintype "passive"))
      (node (ref "U13") (pin "138") (pinfunction "BOOT0_138") (pintype "passive"))
    )
    (net (code "104") (name "Net-(U13A-PDR_ON)") (class "Default")
      (node (ref "R152") (pin "2") (pintype "passive"))
      (node (ref "U13") (pin "143") (pinfunction "PDR_ON_143") (pintype "passive"))
    )
    (net (code "105") (name "Net-(U13A-PH0)") (class "Default")
      (node (ref "R45") (pin "1") (pintype "passive"))
      (node (ref "U13") (pin "23") (pinfunction "PH0_23") (pintype "passive"))
    )
    (net (code "106") (name "Net-(U13A-PH1)") (class "Default")
      (node (ref "C23") (pin "2") (pinfunction "2_2") (pintype "passive"))
      (node (ref "U13") (pin "24") (pinfunction "PH1_24") (pintype "passive"))
      (node (ref "X1") (pin "2") (pinfunction "2_2") (pintype "passive"))
    )
    (net (code "107") (name "Net-(U13B-VCAP_1)") (class "Default")
      (node (ref "C44") (pin "2") (pinfunction "2_2") (pintype "passive"))
      (node (ref "U13") (pin "71") (pinfunction "VCAP_1_71") (pintype "passive"))
    )
    (net (code "108") (name "Net-(U13B-VCAP_2)") (class "Default")
      (node (ref "C59") (pin "2") (pinfunction "2_2") (pintype "passive"))
      (node (ref "U13") (pin "106") (pinfunction "VCAP_2_106") (pintype "passive"))
    )
    (net (code "109") (name "Net-(U13B-VREF+)") (class "Default")
      (node (ref "R40") (pin "1") (pintype "passive"))
      (node (ref "U13") (pin "32") (pinfunction "VREF+_32") (pintype "passive"))
    )
    (net (code "110") (name "VBAT") (class "Default")
      (node (ref "P12") (pin "2") (pinfunction "BP_2") (pintype "passive"))
      (node (ref "U13") (pin "6") (pinfunction "VBAS_6") (pintype "passive"))
    )
    (net (code "111") (name "VCC") (class "Default")
      (node (ref "C12") (pin "2") (pinfunction "2_2") (pintype "passive"))
      (node (ref "C17") (pin "2") (pinfunction "2_2") (pintype "passive"))
      (node (ref "C19") (pin "1") (pinfunction "1_1") (pintype "passive"))
      (node (ref "C45") (pin "1") (pinfunction "1_1") (pintype "passive"))
      (node (ref "C46") (pin "1") (pinfunction "1_1") (pintype "passive"))
      (node (ref "C47") (pin "1") (pinfunction "1_1") (pintype "passive"))
      (node (ref "C48") (pin "1") (pinfunction "1_1") (pintype "passive"))
      (node (ref "C49") (pin "1") (pinfunction "1_1") (pintype "passive"))
      (node (ref "C51") (pin "1") (pinfunction "1_1") (pintype "passive"))
      (node (ref "C52") (pin "2") (pinfunction "2_2") (pintype "passive"))
      (node (ref "C54") (pin "1") (pinfunction "1_1") (pintype "passive"))
      (node (ref "C55") (pin "1") (pinfunction "1_1") (pintype "passive"))
      (node (ref "C56") (pin "1") (pinfunction "1_1") (pintype "passive"))
      (node (ref "C57") (pin "1") (pinfunction "1_1") (pintype "passive"))
      (node (ref "C58") (pin "1") (pinfunction "1_1") (pintype "passive"))
      (node (ref "C60") (pin "1") (pinfunction "1_1") (pintype "passive"))
      (node (ref "D1") (pin "2") (pinfunction "2_2") (pintype "passive"))
      (node (ref "D2") (pin "2") (pinfunction "2_2") (pintype "passive"))
      (node (ref "L4") (pin "1") (pintype "passive"))
      (node (ref "LED1") (pin "2") (pinfunction "2_2") (pintype "passive"))
      (node (ref "LED11") (pin "2") (pinfunction "2_2") (pintype "passive"))
      (node (ref "LED12") (pin "2") (pinfunction "2_2") (pintype "passive"))
      (node (ref "LED13") (pin "2") (pinfunction "2_2") (pintype "passive"))
      (node (ref "LED14") (pin "2") (pinfunction "2_2") (pintype "passive"))
      (node (ref "LED2") (pin "2") (pinfunction "2_2") (pintype "passive"))
      (node (ref "P1") (pin "1") (pinfunction "1_1") (pintype "passive"))
      (node (ref "P2") (pin "1") (pinfunction "1_1") (pintype "passive"))
      (node (ref "P6") (pin "5") (pinfunction "SCLK/CLK_5") (pintype "passive"))
      (node (ref "P7") (pin "1") (pinfunction "1_1") (pintype "passive"))
      (node (ref "R11") (pin "2") (pintype "passive"))
      (node (ref "R12") (pin "2") (pintype "passive"))
      (node (ref "R151") (pin "1") (pintype "passive"))
      (node (ref "R152") (pin "1") (pintype "passive"))
      (node (ref "R57") (pin "2") (pintype "passive"))
      (node (ref "R60") (pin "2") (pintype "passive"))
      (node (ref "R63") (pin "1") (pintype "passive"))
      (node (ref "R65") (pin "1") (pintype "passive"))
      (node (ref "R66") (pin "1") (pintype "passive"))
      (node (ref "R67") (pin "2") (pintype "passive"))
      (node (ref "R68") (pin "2") (pintype "passive"))
      (node (ref "R74") (pin "2") (pintype "passive"))
      (node (ref "R78") (pin "2") (pintype "passive"))
      (node (ref "U13") (pin "108") (pinfunction "VDD_108") (pintype "passive"))
      (node (ref "U13") (pin "121") (pinfunction "VDD_121") (pintype "passive"))
      (node (ref "U13") (pin "131") (pinfunction "VDD_131") (pintype "passive"))
      (node (ref "U13") (pin "144") (pinfunction "VDD_144") (pintype "passive"))
      (node (ref "U13") (pin "17") (pinfunction "VDD_17") (pintype "passive"))
      (node (ref "U13") (pin "30") (pinfunction "VDD_30") (pintype "passive"))
      (node (ref "U13") (pin "39") (pinfunction "VDD_39") (pintype "passive"))
      (node (ref "U13") (pin "52") (pinfunction "VDD_52") (pintype "passive"))
      (node (ref "U13") (pin "62") (pinfunction "VDD_62") (pintype "passive"))
      (node (ref "U13") (pin "72") (pinfunction "VDD_72") (pintype "passive"))
      (node (ref "U13") (pin "84") (pinfunction "VDD_84") (pintype "passive"))
      (node (ref "U13") (pin "95") (pinfunction "VDD_95") (pintype "passive"))
      (node (ref "U18") (pin "8") (pinfunction "VCC_8") (pintype "passive"))
      (node (ref "U46") (pin "14") (pinfunction "VCC_14") (pintype "power_in"))
    )
    (net (code "112") (name "unconnected-(P7-Pad7)") (class "Default")
      (node (ref "P7") (pin "7") (pinfunction "7_7") (pintype "passive+no_connect"))
    )
    (net (code "113") (name "unconnected-(U13A-PA1-Pad35)") (class "Default")
      (node (ref "U13") (pin "35") (pinfunction "PA1_35") (pintype "passive"))
    )
    (net (code "114") (name "unconnected-(U13A-PA2-Pad36)") (class "Default")
      (node (ref "U13") (pin "36") (pinfunction "PA2_36") (pintype "passive"))
    )
    (net (code "115") (name "unconnected-(U13A-PA4-Pad40)") (class "Default")
      (node (ref "U13") (pin "40") (pinfunction "PA4_40") (pintype "passive"))
    )
    (net (code "116") (name "unconnected-(U13A-PA7-Pad43)") (class "Default")
      (node (ref "U13") (pin "43") (pinfunction "PA7_43") (pintype "passive"))
    )
    (net (code "117") (name "unconnected-(U13A-PA8-Pad100)") (class "Default")
      (node (ref "U13") (pin "100") (pinfunction "PA8_100") (pintype "passive"))
    )
    (net (code "118") (name "unconnected-(U13A-PB2-Pad48)") (class "Default")
      (node (ref "U13") (pin "48") (pinfunction "PB2_48") (pintype "passive"))
    )
    (net (code "119") (name "unconnected-(U13A-PB12-Pad73)") (class "Default")
      (node (ref "U13") (pin "73") (pinfunction "PB12_73") (pintype "passive"))
    )
    (net (code "120") (name "unconnected-(U13A-PB13-Pad74)") (class "Default")
      (node (ref "U13") (pin "74") (pinfunction "PB13_74") (pintype "passive"))
    )
    (net (code "121") (name "unconnected-(U13A-PB14-Pad75)") (class "Default")
      (node (ref "U13") (pin "75") (pinfunction "PB14_75") (pintype "passive"))
    )
    (net (code "122") (name "unconnected-(U13A-PB15-Pad76)") (class "Default")
      (node (ref "U13") (pin "76") (pinfunction "PB15_76") (pintype "passive"))
    )
    (net (code "123") (name "unconnected-(U13A-PC0-Pad26)") (class "Default")
      (node (ref "U13") (pin "26") (pinfunction "PC0_26") (pintype "passive"))
    )
    (net (code "124") (name "unconnected-(U13A-PC1-Pad27)") (class "Default")
      (node (ref "U13") (pin "27") (pinfunction "PC1_27") (pintype "passive"))
    )
    (net (code "125") (name "unconnected-(U13A-PC4-Pad44)") (class "Default")
      (node (ref "U13") (pin "44") (pinfunction "PC4_44") (pintype "passive"))
    )
    (net (code "126") (name "unconnected-(U13A-PC5-Pad45)") (class "Default")
      (node (ref "U13") (pin "45") (pinfunction "PC5_45") (pintype "passive"))
    )
    (net (code "127") (name "unconnected-(U13A-PD7-Pad123)") (class "Default")
      (node (ref "U13") (pin "123") (pinfunction "PD7_123") (pintype "passive"))
    )
    (net (code "128") (name "unconnected-(U13A-PD10-Pad79)") (class "Default")
      (node (ref "U13") (pin "79") (pinfunction "PD10_79") (pintype "passive"))
    )
    (net (code "129") (name "unconnected-(U13A-PD14-Pad85)") (class "Default")
      (node (ref "U13") (pin "85") (pinfunction "PD14_85") (pintype "passive"))
    )
    (net (code "130") (name "unconnected-(U13A-PD15-Pad86)") (class "Default")
      (node (ref "U13") (pin "86") (pinfunction "PD15_86") (pintype "passive"))
    )
    (net (code "131") (name "unconnected-(U13A-PE4-Pad3)") (class "Default")
      (node (ref "U13") (pin "3") (pinfunction "PE4_3") (pintype "passive"))
    )
    (net (code "132") (name "unconnected-(U13A-PF11-Pad49)") (class "Default")
      (node (ref "U13") (pin "49") (pinfunction "PF11_49") (pintype "passive"))
    )
    (net (code "133") (name "unconnected-(U13A-PF12-Pad50)") (class "Default")
      (node (ref "U13") (pin "50") (pinfunction "PF12_50") (pintype "passive"))
    )
    (net (code "134") (name "unconnected-(U13A-PG6-Pad91)") (class "Default")
      (node (ref "U13") (pin "91") (pinfunction "PG6_91") (pintype "passive"))
    )
    (net (code "135") (name "unconnected-(U13A-PG7-Pad92)") (class "Default")
      (node (ref "U13") (pin "92") (pinfunction "PG7_92") (pintype "passive"))
    )
    (net (code "136") (name "unconnected-(U13A-PG8-Pad93)") (class "Default")
      (node (ref "U13") (pin "93") (pinfunction "PG8_93") (pintype "passive"))
    )
    (net (code "137") (name "unconnected-(U13A-PG10-Pad125)") (class "Default")
      (node (ref "U13") (pin "125") (pinfunction "PG10_125") (pintype "passive"))
    )
    (net (code "138") (name "unconnected-(U13A-PG11-Pad126)") (class "Default")
      (node (ref "U13") (pin "126") (pinfunction "PG11_126") (pintype "passive"))
    )
    (net (code "139") (name "unconnected-(U13A-PG12-Pad127)") (class "Default")
      (node (ref "U13") (pin "127") (pinfunction "PG12_127") (pintype "passive"))
    )
    (net (code "140") (name "unconnected-(U13A-PG13-Pad128)") (class "Default")
      (node (ref "U13") (pin "128") (pinfunction "PG13_128") (pintype "passive"))
    )
    (net (code "141") (name "unconnected-(U13A-PG14-Pad129)") (class "Default")
      (node (ref "U13") (pin "129") (pinfunction "PG14_129") (pintype "passive"))
    )
    (net (code "142") (name "unconnected-(U13A-PG15-Pad132)") (class "Default")
      (node (ref "U13") (pin "132") (pinfunction "PG15_132") (pintype "passive"))
    )
    (net (code "143") (name "unconnected-(U46A-Y-Pad2)") (class "Default")
      (node (ref "U46") (pin "2") (pinfunction "Y_2") (pintype "output"))
    )
    (net (code "144") (name "unconnected-(U46D-Y-Pad8)") (class "Default")
      (node (ref "U46") (pin "8") (pinfunction "Y_8") (pintype "output"))
    )
    (net (code "145") (name "unconnected-(U46E-Y-Pad10)") (class "Default")
      (node (ref "U46") (pin "10") (pinfunction "Y_10") (pintype "output"))
    )
    (net (code "146") (name "unconnected-(U46F-Y-Pad12)") (class "Default")
      (node (ref "U46") (pin "12") (pinfunction "Y_12") (pintype "output"))
    )
  )
)
